# Power_Distribution_v2.net
KiCad netlist of a schematic drawn in EAGLE
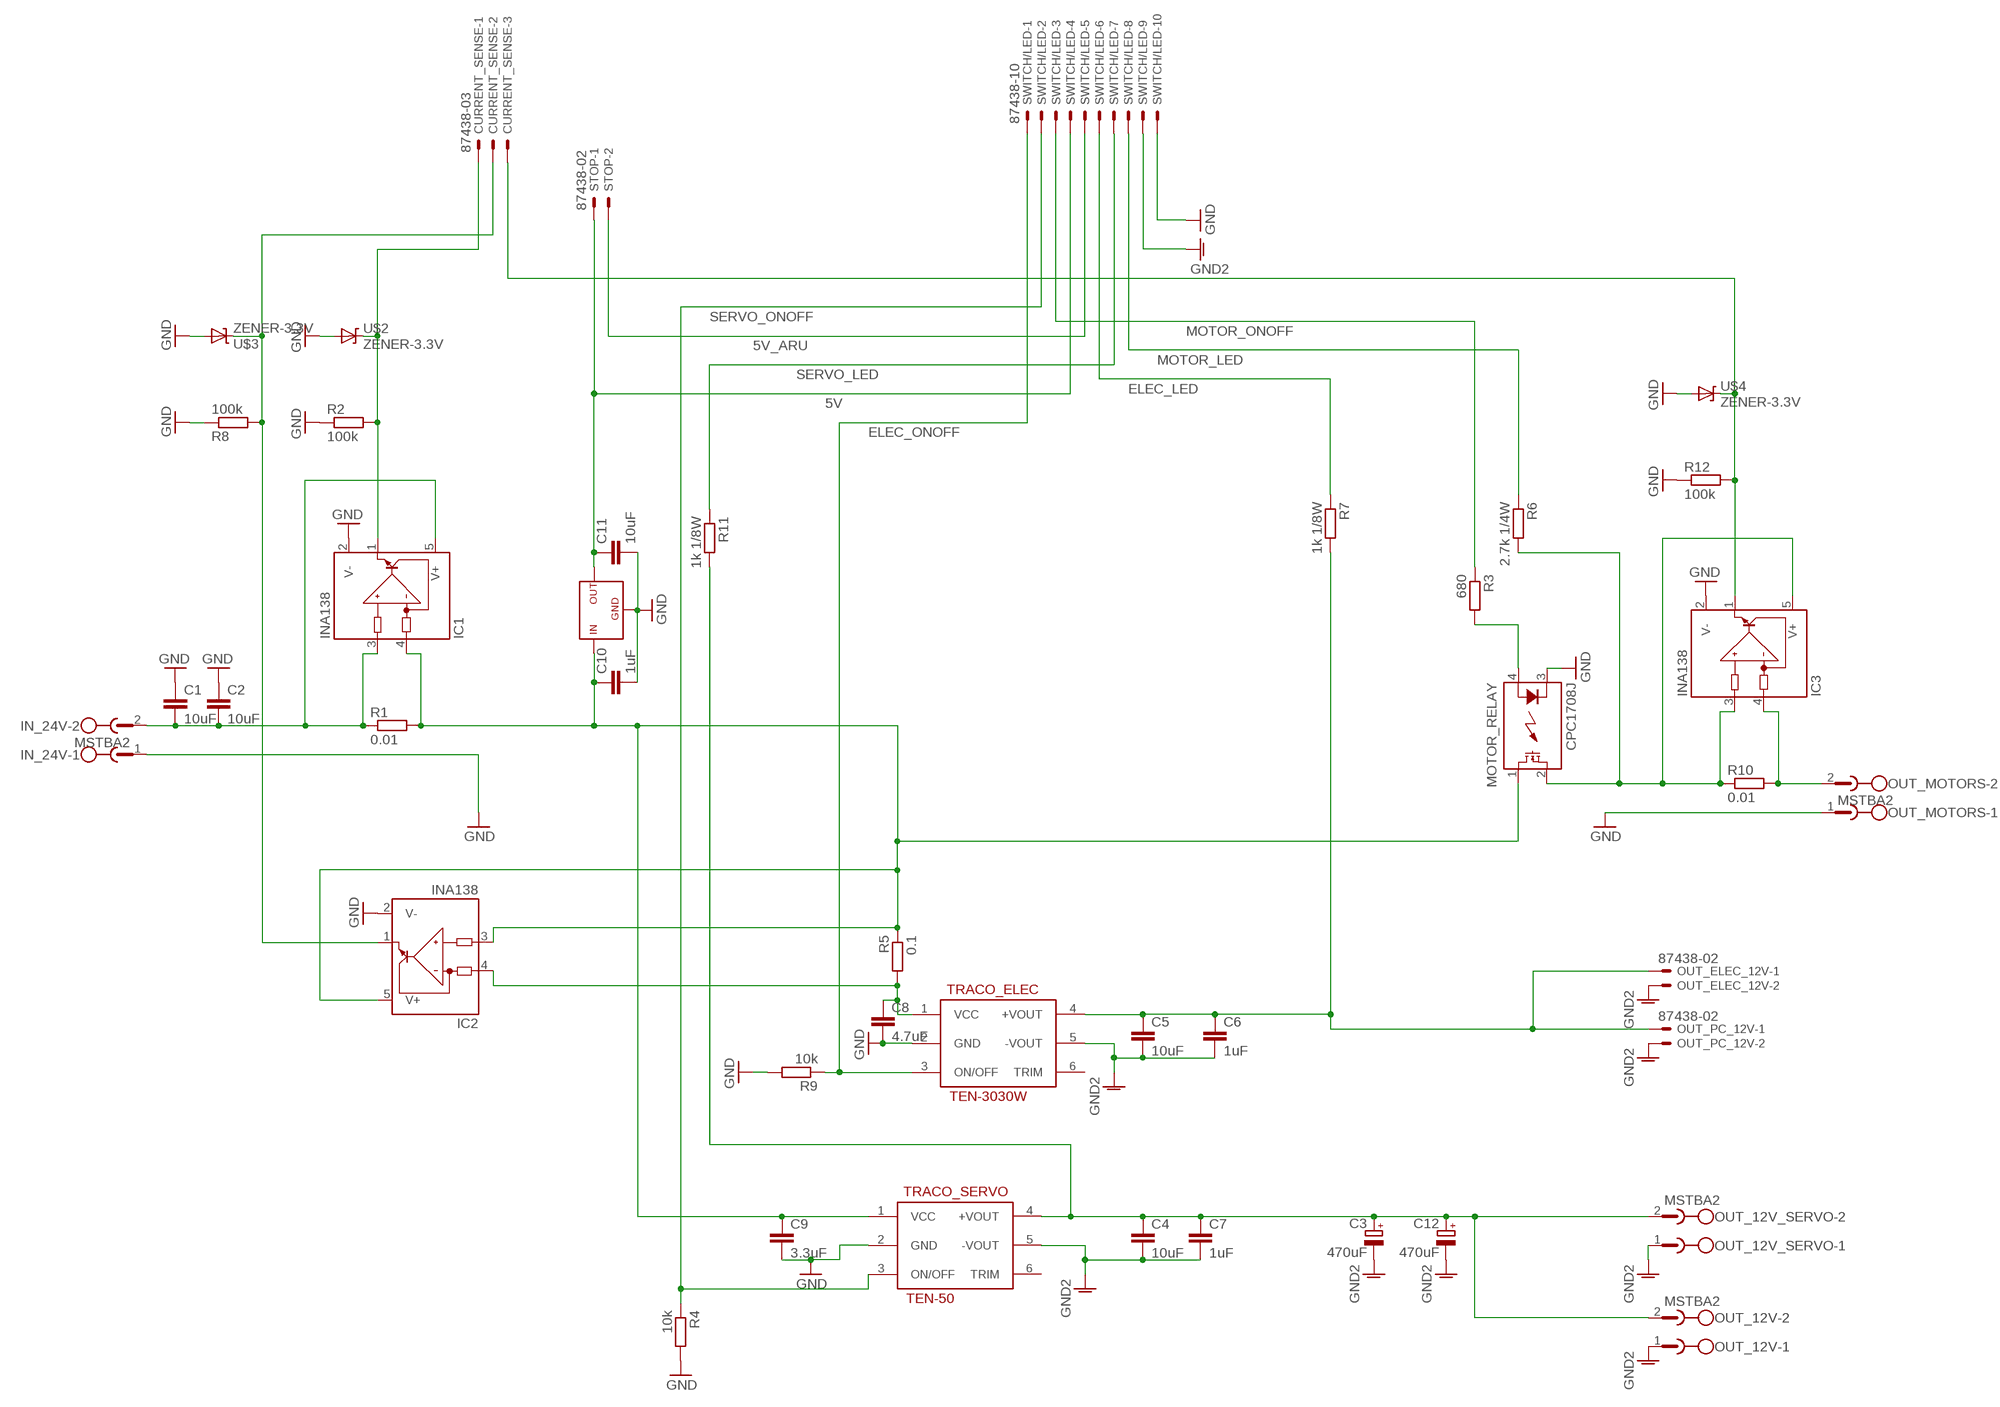
[diagram p0: schematic, sheet 1]

(export (version "E")
  (design (tool "Eeschema 10.0.6"))
  (components
    (comp (ref "C1")
      (value "10uF")
      (footprint "eagle-import:C1812")
      (libsource (lib "eagle-import") (part "C-EUC1812"))
    )
    (comp (ref "C2")
      (value "10uF")
      (footprint "eagle-import:C1812")
      (libsource (lib "eagle-import") (part "C-EUC1812"))
    )
    (comp (ref "C3")
      (value "470uF")
      (footprint "eagle-import:E5-10,5")
      (libsource (lib "eagle-import") (part "CPOL-EUE5-10.5"))
    )
    (comp (ref "C4")
      (value "10uF")
      (footprint "eagle-import:C1812")
      (libsource (lib "eagle-import") (part "C-EUC1812"))
    )
    (comp (ref "C5")
      (value "10uF")
      (footprint "eagle-import:C1812")
      (libsource (lib "eagle-import") (part "C-EUC1812"))
    )
    (comp (ref "C6")
      (value "1uF")
      (footprint "eagle-import:C0805")
      (libsource (lib "eagle-import") (part "C-EUC0805"))
    )
    (comp (ref "C7")
      (value "1uF")
      (footprint "eagle-import:C0805")
      (libsource (lib "eagle-import") (part "C-EUC0805"))
    )
    (comp (ref "C8")
      (value "4.7uF")
      (footprint "eagle-import:C1210")
      (libsource (lib "eagle-import") (part "C-EUC1210"))
    )
    (comp (ref "C9")
      (value "3.3uF")
      (footprint "eagle-import:C1210")
      (libsource (lib "eagle-import") (part "C-EUC1210"))
    )
    (comp (ref "C10")
      (value "1uF")
      (footprint "eagle-import:C0805")
      (libsource (lib "eagle-import") (part "C-EUC0805"))
    )
    (comp (ref "C11")
      (value "10uF")
      (footprint "eagle-import:C0805")
      (libsource (lib "eagle-import") (part "C-EUC0805"))
    )
    (comp (ref "C12")
      (value "470uF")
      (footprint "eagle-import:E5-10,5")
      (libsource (lib "eagle-import") (part "CPOL-EUE5-10.5"))
    )
    (comp (ref "CURRENT_SENSE")
      (value "87438-03")
      (footprint "eagle-import:87438-03")
      (libsource (lib "eagle-import") (part "87438-03"))
    )
    (comp (ref "IC1")
      (value "INA138")
      (footprint "eagle-import:SOT23-5")
      (fields (field (name "MF") "TEXAS INSTRUMENTS") (field (name "MPN") "INA138NA/250"))
      (libsource (lib "eagle-import") (part "INA138"))
    )
    (comp (ref "IC2")
      (value "INA138")
      (footprint "eagle-import:SOT23-5")
      (fields (field (name "MF") "TEXAS INSTRUMENTS") (field (name "MPN") "INA138NA/250"))
      (libsource (lib "eagle-import") (part "INA138"))
    )
    (comp (ref "IC3")
      (value "INA138")
      (footprint "eagle-import:SOT23-5")
      (fields (field (name "MF") "TEXAS INSTRUMENTS") (field (name "MPN") "INA138NA/250"))
      (libsource (lib "eagle-import") (part "INA138"))
    )
    (comp (ref "IN_24V")
      (value "MSTBA2")
      (footprint "eagle-import:MSTBA2")
      (fields (field (name "MF") "FARNELL") (field (name "MPN") "1757242"))
      (libsource (lib "eagle-import") (part "MSTBA2"))
    )
    (comp (ref "MOTOR_RELAY")
      (value "CPC1708J")
      (footprint "eagle-import:I4-PAC")
      (libsource (lib "eagle-import") (part "CPC1708J"))
    )
    (comp (ref "OUT_12V")
      (value "MSTBA2")
      (footprint "eagle-import:MSTBA2")
      (fields (field (name "MF") "FARNELL") (field (name "MPN") "1757242"))
      (libsource (lib "eagle-import") (part "MSTBA2"))
    )
    (comp (ref "OUT_12V_SERVO")
      (value "MSTBA2")
      (footprint "eagle-import:MSTBA2")
      (fields (field (name "MF") "FARNELL") (field (name "MPN") "1757242"))
      (libsource (lib "eagle-import") (part "MSTBA2"))
    )
    (comp (ref "OUT_ELEC_12V")
      (value "87438-02")
      (footprint "eagle-import:87438-02")
      (libsource (lib "eagle-import") (part "87438-02"))
    )
    (comp (ref "OUT_MOTORS")
      (value "MSTBA2")
      (footprint "eagle-import:MSTBA2")
      (fields (field (name "MF") "FARNELL") (field (name "MPN") "1757242"))
      (libsource (lib "eagle-import") (part "MSTBA2"))
    )
    (comp (ref "OUT_PC_12V")
      (value "87438-02")
      (footprint "eagle-import:87438-02")
      (libsource (lib "eagle-import") (part "87438-02"))
    )
    (comp (ref "R1")
      (value "0.01")
      (footprint "eagle-import:R2010")
      (libsource (lib "eagle-import") (part "R-EU_R2010"))
    )
    (comp (ref "R2")
      (value "100k")
      (footprint "eagle-import:R0603")
      (libsource (lib "eagle-import") (part "R-EU_R0603"))
    )
    (comp (ref "R3")
      (value "680")
      (footprint "eagle-import:R0603")
      (libsource (lib "eagle-import") (part "R-EU_R0603"))
    )
    (comp (ref "R4")
      (value "10k")
      (footprint "eagle-import:R0603")
      (libsource (lib "eagle-import") (part "R-EU_R0603"))
    )
    (comp (ref "R5")
      (value "0.1")
      (footprint "eagle-import:R2010")
      (libsource (lib "eagle-import") (part "R-EU_R2010"))
    )
    (comp (ref "R6")
      (value "2.7k 1/4W")
      (footprint "eagle-import:R1206")
      (libsource (lib "eagle-import") (part "R-EU_R1206"))
    )
    (comp (ref "R7")
      (value "1k 1/8W")
      (footprint "eagle-import:R0603")
      (libsource (lib "eagle-import") (part "R-EU_R0603"))
    )
    (comp (ref "R8")
      (value "100k")
      (footprint "eagle-import:R0603")
      (libsource (lib "eagle-import") (part "R-EU_R0603"))
    )
    (comp (ref "R9")
      (value "10k")
      (footprint "eagle-import:R0603")
      (libsource (lib "eagle-import") (part "R-EU_R0603"))
    )
    (comp (ref "R10")
      (value "0.01")
      (footprint "eagle-import:R2010")
      (libsource (lib "eagle-import") (part "R-EU_R2010"))
    )
    (comp (ref "R11")
      (value "1k 1/8W")
      (footprint "eagle-import:R0603")
      (libsource (lib "eagle-import") (part "R-EU_R0603"))
    )
    (comp (ref "R12")
      (value "100k")
      (footprint "eagle-import:R0603")
      (libsource (lib "eagle-import") (part "R-EU_R0603"))
    )
    (comp (ref "STOP")
      (value "87438-02")
      (footprint "eagle-import:87438-02")
      (libsource (lib "eagle-import") (part "87438-02"))
    )
    (comp (ref "SWITCH/LED")
      (value "87438-10")
      (footprint "eagle-import:87438-10")
      (libsource (lib "eagle-import") (part "87438-10"))
    )
    (comp (ref "TRACO_ELEC")
      (value "TEN-3030W")
      (footprint "eagle-import:TRACO2X1")
      (libsource (lib "eagle-import") (part "TEN-3030W"))
    )
    (comp (ref "TRACO_SERVO")
      (value "TEN-50")
      (footprint "eagle-import:TRACO2X1_50W")
      (libsource (lib "eagle-import") (part "TEN-3050W"))
    )
    (comp (ref "U$1")
      (value "MIC5239")
      (footprint "eagle-import:SOT-223")
      (libsource (lib "eagle-import") (part "MIC5239"))
    )
    (comp (ref "U$2")
      (value "ZENER-3.3V")
      (footprint "eagle-import:SOD-323")
      (libsource (lib "eagle-import") (part "DIODE-ZENER-BZT52"))
    )
    (comp (ref "U$3")
      (value "ZENER-3.3V")
      (footprint "eagle-import:SOD-323")
      (libsource (lib "eagle-import") (part "DIODE-ZENER-BZT52"))
    )
    (comp (ref "U$4")
      (value "ZENER-3.3V")
      (footprint "eagle-import:SOD-323")
      (libsource (lib "eagle-import") (part "DIODE-ZENER-BZT52"))
    )
  )
  (nets
    (net (code "1") (name "/5V") (class "Default")
      (node (ref "C11") (pin "1") (pinfunction "1_1") (pintype "passive"))
      (node (ref "STOP") (pin "1") (pinfunction "S_1") (pintype "passive"))
      (node (ref "SWITCH/LED") (pin "4") (pinfunction "S_4") (pintype "passive"))
      (node (ref "U$1") (pin "3") (pinfunction "OUT_3") (pintype "bidirectional"))
    )
    (net (code "2") (name "/5V_ARU") (class "Default")
      (node (ref "STOP") (pin "2") (pinfunction "S_2") (pintype "passive"))
      (node (ref "SWITCH/LED") (pin "5") (pinfunction "S_5") (pintype "passive"))
    )
    (net (code "3") (name "/ELEC_LED") (class "Default")
      (node (ref "R7") (pin "1") (pinfunction "1_1") (pintype "passive"))
      (node (ref "SWITCH/LED") (pin "6") (pinfunction "S_6") (pintype "passive"))
    )
    (net (code "4") (name "/ELEC_ONOFF") (class "Default")
      (node (ref "R9") (pin "1") (pinfunction "1_1") (pintype "passive"))
      (node (ref "SWITCH/LED") (pin "1") (pinfunction "S_1") (pintype "passive"))
      (node (ref "TRACO_ELEC") (pin "3") (pinfunction "ON/OFF_3") (pintype "bidirectional"))
    )
    (net (code "5") (name "/MOTOR_LED") (class "Default")
      (node (ref "R6") (pin "1") (pinfunction "1_1") (pintype "passive"))
      (node (ref "SWITCH/LED") (pin "8") (pinfunction "S_8") (pintype "passive"))
    )
    (net (code "6") (name "/MOTOR_ONOFF") (class "Default")
      (node (ref "R3") (pin "1") (pinfunction "1_1") (pintype "passive"))
      (node (ref "SWITCH/LED") (pin "3") (pinfunction "S_3") (pintype "passive"))
    )
    (net (code "7") (name "/SERVO_LED") (class "Default")
      (node (ref "R11") (pin "1") (pinfunction "1_1") (pintype "passive"))
      (node (ref "SWITCH/LED") (pin "7") (pinfunction "S_7") (pintype "passive"))
    )
    (net (code "8") (name "/SERVO_ONOFF") (class "Default")
      (node (ref "R4") (pin "1") (pinfunction "1_1") (pintype "passive"))
      (node (ref "SWITCH/LED") (pin "2") (pinfunction "S_2") (pintype "passive"))
      (node (ref "TRACO_SERVO") (pin "3") (pinfunction "ON/OFF_3") (pintype "bidirectional"))
    )
    (net (code "9") (name "GND") (class "Default")
      (node (ref "C1") (pin "1") (pinfunction "1_1") (pintype "passive"))
      (node (ref "C10") (pin "2") (pinfunction "2_2") (pintype "passive"))
      (node (ref "C11") (pin "2") (pinfunction "2_2") (pintype "passive"))
      (node (ref "C2") (pin "1") (pinfunction "1_1") (pintype "passive"))
      (node (ref "C8") (pin "2") (pinfunction "2_2") (pintype "passive"))
      (node (ref "C9") (pin "2") (pinfunction "2_2") (pintype "passive"))
      (node (ref "IC1") (pin "2") (pinfunction "V-_2") (pintype "power_in"))
      (node (ref "IC2") (pin "2") (pinfunction "V-_2") (pintype "power_in"))
      (node (ref "IC3") (pin "2") (pinfunction "V-_2") (pintype "power_in"))
      (node (ref "IN_24V") (pin "1") (pinfunction "1_1") (pintype "passive"))
      (node (ref "MOTOR_RELAY") (pin "3") (pinfunction "K_3") (pintype "passive"))
      (node (ref "OUT_MOTORS") (pin "1") (pinfunction "1_1") (pintype "passive"))
      (node (ref "R12") (pin "1") (pinfunction "1_1") (pintype "passive"))
      (node (ref "R2") (pin "1") (pinfunction "1_1") (pintype "passive"))
      (node (ref "R4") (pin "2") (pinfunction "2_2") (pintype "passive"))
      (node (ref "R8") (pin "1") (pinfunction "1_1") (pintype "passive"))
      (node (ref "R9") (pin "2") (pinfunction "2_2") (pintype "passive"))
      (node (ref "SWITCH/LED") (pin "10") (pinfunction "S_10") (pintype "passive"))
      (node (ref "TRACO_ELEC") (pin "2") (pinfunction "GND_2") (pintype "bidirectional"))
      (node (ref "TRACO_SERVO") (pin "2") (pinfunction "GND_2") (pintype "bidirectional"))
      (node (ref "U$1") (pin "2") (pinfunction "GND_2") (pintype "bidirectional"))
      (node (ref "U$1") (pin "4") (pinfunction "GND_4") (pintype "bidirectional"))
      (node (ref "U$2") (pin "2") (pinfunction "A_2") (pintype "passive"))
      (node (ref "U$3") (pin "2") (pinfunction "A_2") (pintype "passive"))
      (node (ref "U$4") (pin "2") (pinfunction "A_2") (pintype "passive"))
    )
    (net (code "10") (name "GND2") (class "Default")
      (node (ref "C12") (pin "-") (pinfunction "-_-") (pintype "passive"))
      (node (ref "C3") (pin "-") (pinfunction "-_-") (pintype "passive"))
      (node (ref "C4") (pin "2") (pinfunction "2_2") (pintype "passive"))
      (node (ref "C5") (pin "2") (pinfunction "2_2") (pintype "passive"))
      (node (ref "C6") (pin "2") (pinfunction "2_2") (pintype "passive"))
      (node (ref "C7") (pin "2") (pinfunction "2_2") (pintype "passive"))
      (node (ref "OUT_12V") (pin "1") (pinfunction "1_1") (pintype "passive"))
      (node (ref "OUT_12V_SERVO") (pin "1") (pinfunction "1_1") (pintype "passive"))
      (node (ref "OUT_ELEC_12V") (pin "2") (pinfunction "S_2") (pintype "passive"))
      (node (ref "OUT_PC_12V") (pin "2") (pinfunction "S_2") (pintype "passive"))
      (node (ref "SWITCH/LED") (pin "9") (pinfunction "S_9") (pintype "passive"))
      (node (ref "TRACO_ELEC") (pin "5") (pinfunction "-VOUT_5") (pintype "bidirectional"))
      (node (ref "TRACO_SERVO") (pin "5") (pinfunction "-VOUT_5") (pintype "bidirectional"))
    )
    (net (code "11") (name "Net-(CURRENT_SENSEA-S)") (class "Default")
      (node (ref "CURRENT_SENSE") (pin "1") (pinfunction "S_1") (pintype "passive"))
      (node (ref "IC1") (pin "1") (pinfunction "OUT_1") (pintype "output"))
      (node (ref "R2") (pin "2") (pinfunction "2_2") (pintype "passive"))
      (node (ref "U$2") (pin "1") (pinfunction "C_1") (pintype "passive"))
    )
    (net (code "12") (name "Net-(CURRENT_SENSEB-S)") (class "Default")
      (node (ref "CURRENT_SENSE") (pin "2") (pinfunction "S_2") (pintype "passive"))
      (node (ref "IC2") (pin "1") (pinfunction "OUT_1") (pintype "output"))
      (node (ref "R8") (pin "2") (pinfunction "2_2") (pintype "passive"))
      (node (ref "U$3") (pin "1") (pinfunction "C_1") (pintype "passive"))
    )
    (net (code "13") (name "Net-(CURRENT_SENSEC-S)") (class "Default")
      (node (ref "CURRENT_SENSE") (pin "3") (pinfunction "S_3") (pintype "passive"))
      (node (ref "IC3") (pin "1") (pinfunction "OUT_1") (pintype "output"))
      (node (ref "R12") (pin "2") (pinfunction "2_2") (pintype "passive"))
      (node (ref "U$4") (pin "1") (pinfunction "C_1") (pintype "passive"))
    )
    (net (code "14") (name "Net-(IC1-IN+)") (class "Default")
      (node (ref "C1") (pin "2") (pinfunction "2_2") (pintype "passive"))
      (node (ref "C2") (pin "2") (pinfunction "2_2") (pintype "passive"))
      (node (ref "IC1") (pin "3") (pinfunction "IN+_3") (pintype "input"))
      (node (ref "IC1") (pin "5") (pinfunction "V+_5") (pintype "power_in"))
      (node (ref "IN_24V") (pin "2") (pinfunction "1_2") (pintype "passive"))
      (node (ref "R1") (pin "1") (pinfunction "1_1") (pintype "passive"))
    )
    (net (code "15") (name "Net-(IC1-IN-)") (class "Default")
      (node (ref "C10") (pin "1") (pinfunction "1_1") (pintype "passive"))
      (node (ref "C9") (pin "1") (pinfunction "1_1") (pintype "passive"))
      (node (ref "IC1") (pin "4") (pinfunction "IN-_4") (pintype "input"))
      (node (ref "IC2") (pin "3") (pinfunction "IN+_3") (pintype "input"))
      (node (ref "IC2") (pin "5") (pinfunction "V+_5") (pintype "power_in"))
      (node (ref "MOTOR_RELAY") (pin "1") (pinfunction "DS1_1") (pintype "passive"))
      (node (ref "R1") (pin "2") (pinfunction "2_2") (pintype "passive"))
      (node (ref "R5") (pin "1") (pinfunction "1_1") (pintype "passive"))
      (node (ref "TRACO_SERVO") (pin "1") (pinfunction "VCC_1") (pintype "bidirectional"))
      (node (ref "U$1") (pin "1") (pinfunction "IN_1") (pintype "bidirectional"))
    )
    (net (code "16") (name "Net-(IC2-IN-)") (class "Default")
      (node (ref "C8") (pin "1") (pinfunction "1_1") (pintype "passive"))
      (node (ref "IC2") (pin "4") (pinfunction "IN-_4") (pintype "input"))
      (node (ref "R5") (pin "2") (pinfunction "2_2") (pintype "passive"))
      (node (ref "TRACO_ELEC") (pin "1") (pinfunction "VCC_1") (pintype "bidirectional"))
    )
    (net (code "17") (name "Net-(IC3-IN+)") (class "Default")
      (node (ref "IC3") (pin "3") (pinfunction "IN+_3") (pintype "input"))
      (node (ref "IC3") (pin "5") (pinfunction "V+_5") (pintype "power_in"))
      (node (ref "MOTOR_RELAY") (pin "2") (pinfunction "DS2_2") (pintype "passive"))
      (node (ref "R10") (pin "1") (pinfunction "1_1") (pintype "passive"))
      (node (ref "R6") (pin "2") (pinfunction "2_2") (pintype "passive"))
    )
    (net (code "18") (name "Net-(IC3-IN-)") (class "Default")
      (node (ref "IC3") (pin "4") (pinfunction "IN-_4") (pintype "input"))
      (node (ref "OUT_MOTORS") (pin "2") (pinfunction "1_2") (pintype "passive"))
      (node (ref "R10") (pin "2") (pinfunction "2_2") (pintype "passive"))
    )
    (net (code "19") (name "Net-(MOTOR_RELAY-A)") (class "Default")
      (node (ref "MOTOR_RELAY") (pin "4") (pinfunction "A_4") (pintype "passive"))
      (node (ref "R3") (pin "2") (pinfunction "2_2") (pintype "passive"))
    )
    (net (code "20") (name "Net-(OUT_12VB-1)") (class "Default")
      (node (ref "C12") (pin "+") (pinfunction "+_+") (pintype "passive"))
      (node (ref "C3") (pin "+") (pinfunction "+_+") (pintype "passive"))
      (node (ref "C4") (pin "1") (pinfunction "1_1") (pintype "passive"))
      (node (ref "C7") (pin "1") (pinfunction "1_1") (pintype "passive"))
      (node (ref "OUT_12V") (pin "2") (pinfunction "1_2") (pintype "passive"))
      (node (ref "OUT_12V_SERVO") (pin "2") (pinfunction "1_2") (pintype "passive"))
      (node (ref "R11") (pin "2") (pinfunction "2_2") (pintype "passive"))
      (node (ref "TRACO_SERVO") (pin "4") (pinfunction "+VOUT_4") (pintype "bidirectional"))
    )
    (net (code "21") (name "Net-(OUT_ELEC_12VA-S)") (class "Default")
      (node (ref "C5") (pin "1") (pinfunction "1_1") (pintype "passive"))
      (node (ref "C6") (pin "1") (pinfunction "1_1") (pintype "passive"))
      (node (ref "OUT_ELEC_12V") (pin "1") (pinfunction "S_1") (pintype "passive"))
      (node (ref "OUT_PC_12V") (pin "1") (pinfunction "S_1") (pintype "passive"))
      (node (ref "R7") (pin "2") (pinfunction "2_2") (pintype "passive"))
      (node (ref "TRACO_ELEC") (pin "4") (pinfunction "+VOUT_4") (pintype "bidirectional"))
    )
    (net (code "22") (name "unconnected-(TRACO_ELEC-TRIM-Pad6)") (class "Default")
      (node (ref "TRACO_ELEC") (pin "6") (pinfunction "TRIM_6") (pintype "bidirectional"))
    )
    (net (code "23") (name "unconnected-(TRACO_SERVO-TRIM-Pad6)") (class "Default")
      (node (ref "TRACO_SERVO") (pin "6") (pinfunction "TRIM_6") (pintype "bidirectional"))
    )
  )
)
